# RCservo_interface.net
KiCad netlist of a schematic drawn in Altium Designer
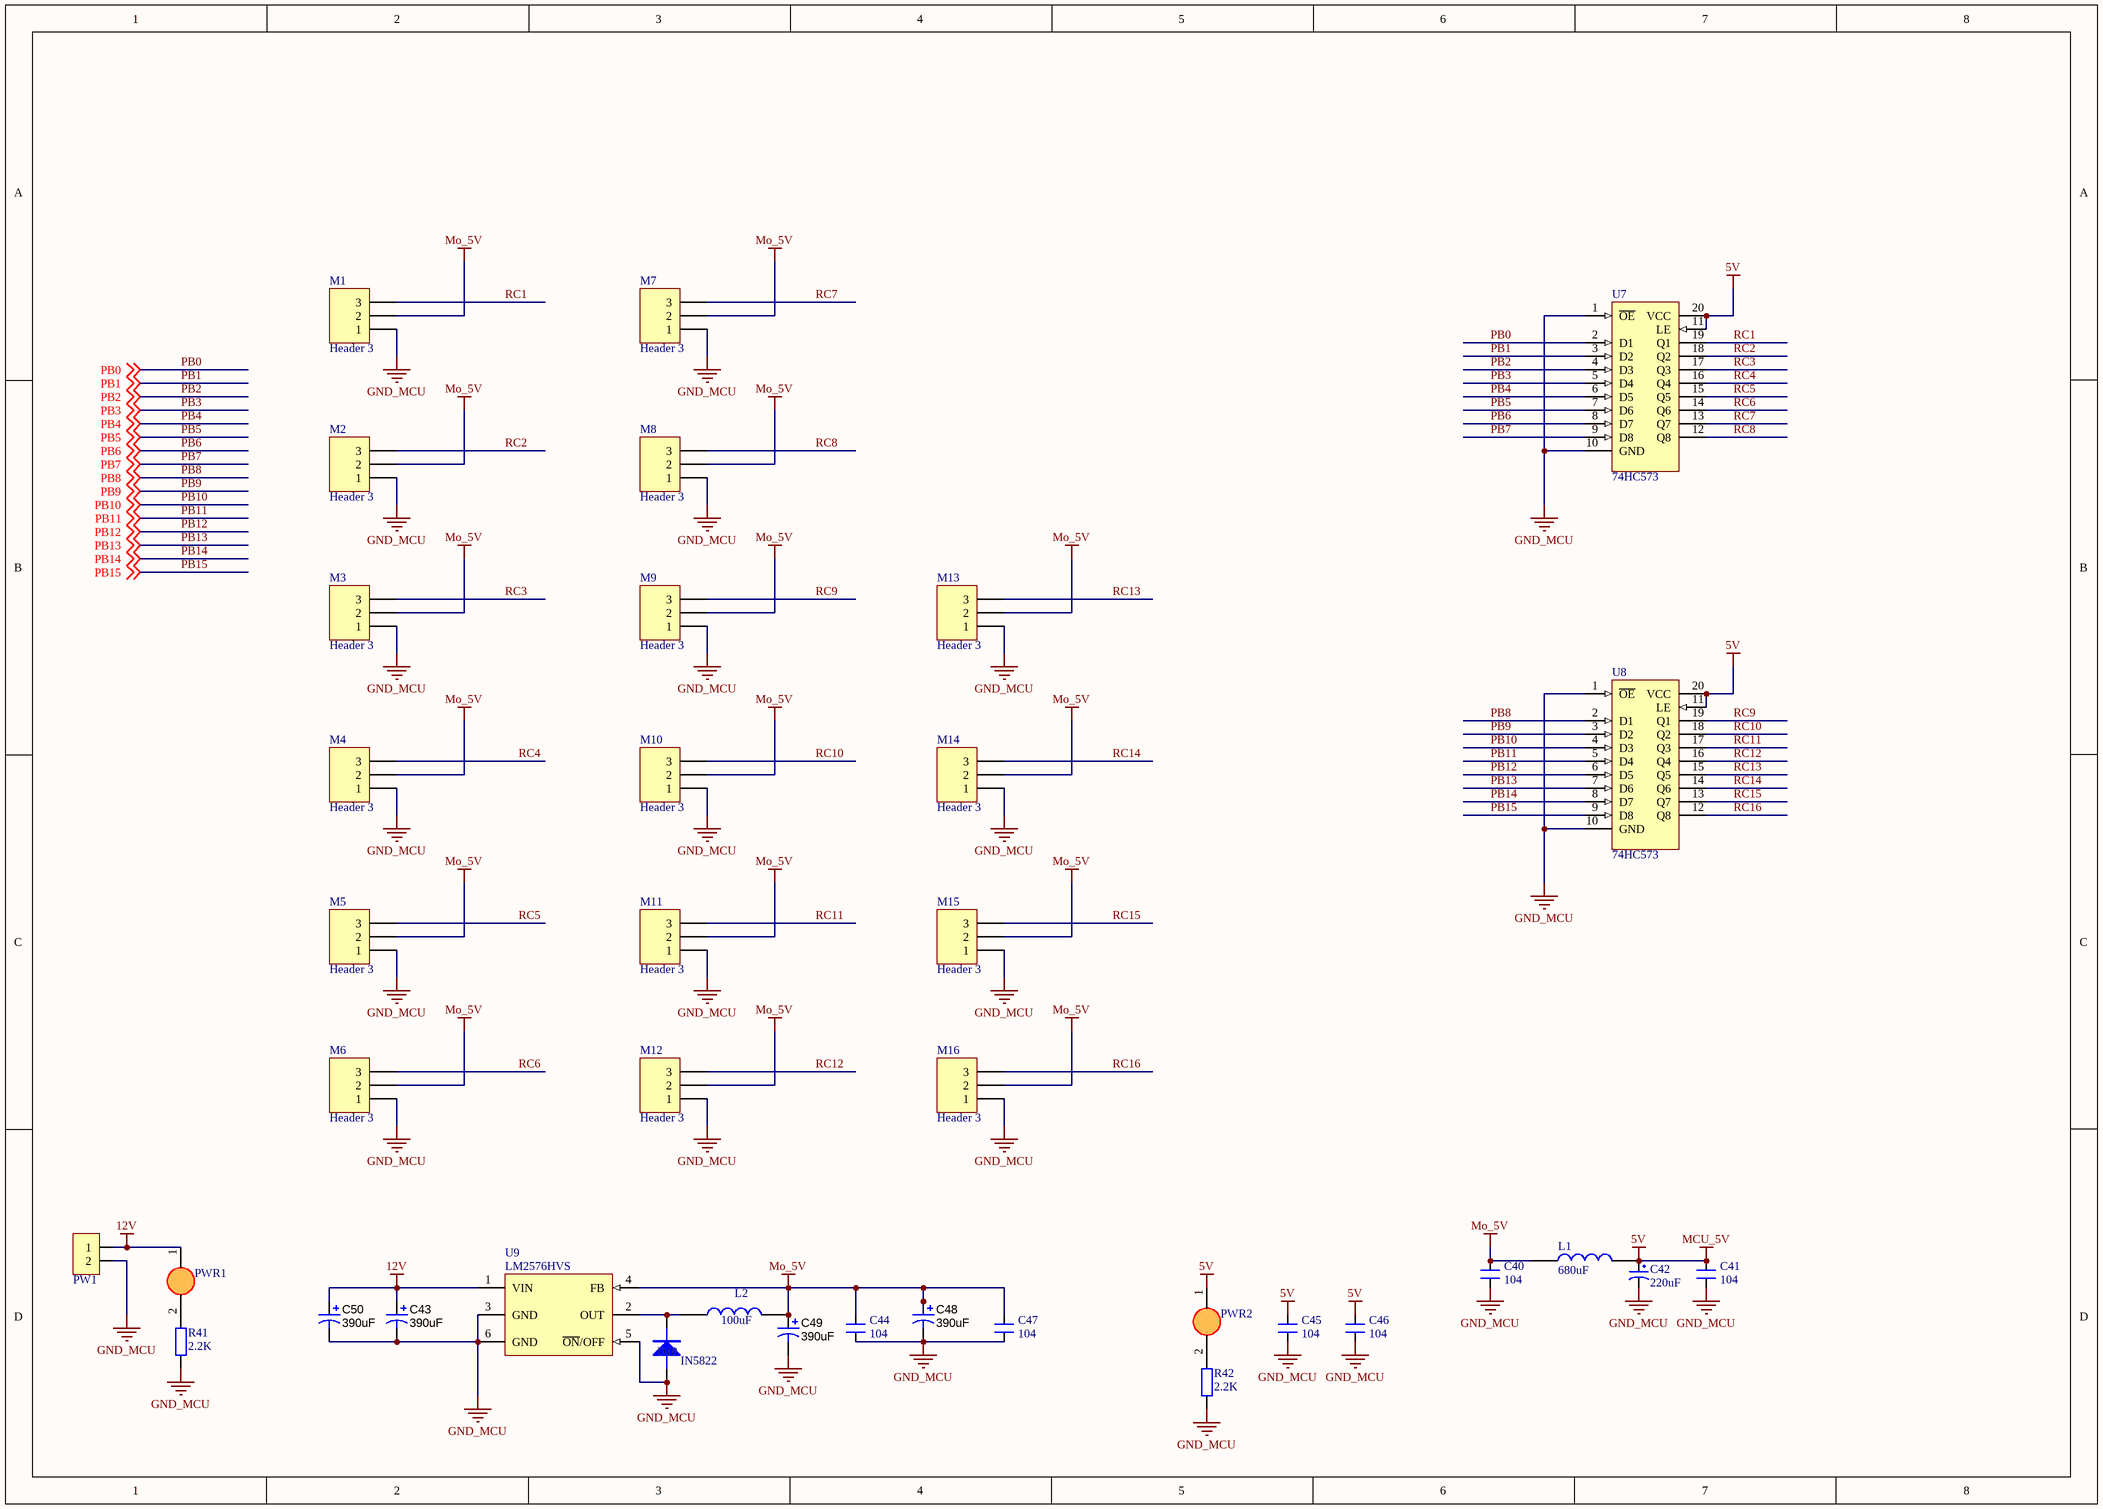
[diagram p0: RCservo_interface.SchDoc]

(export (version "E")
  (design (tool "Eeschema 10.0.6"))
  (components
    (comp (ref "C40")
      (value "104")
      (footprint "0805_HV")
      (description "Cap SMD")
      (libsource (lib "hatcatbietbay") (part "CM"))
    )
    (comp (ref "C41")
      (value "104")
      (footprint "0805_HV")
      (description "Cap SMD")
      (libsource (lib "hatcatbietbay") (part "CM"))
    )
    (comp (ref "C42")
      (value "220uF")
      (footprint "TU_NHOM_2.5_MH")
      (description "TU_NHOM_220uF_25V_MH")
      (libsource (lib "MH_DA_THU_VIEN_16122016") (part "TU_NHOM_220uF_25V_MH"))
    )
    (comp (ref "C43")
      (value "390uF")
      (footprint "CP1/3.0")
      (fields
        (field (name "PARTNUMBER") "UHW1H391MPD6")
        (field (name "MANUFACTURER") "Nichicon")
        (field (name "VALUEDISPLAYED") "390uF")
        (field (name "PUBLISHER") "Texas Instruments")
      )
      (libsource (lib "mySch") (part "Capacitor TuHoa"))
    )
    (comp (ref "C44")
      (value "104")
      (footprint "0805_HV")
      (description "Cap SMD")
      (libsource (lib "hatcatbietbay") (part "CM"))
    )
    (comp (ref "C45")
      (value "104")
      (footprint "0805_HV")
      (description "Cap SMD")
      (libsource (lib "hatcatbietbay") (part "CM"))
    )
    (comp (ref "C46")
      (value "104")
      (footprint "0805_HV")
      (description "Cap SMD")
      (libsource (lib "hatcatbietbay") (part "CM"))
    )
    (comp (ref "C47")
      (value "104")
      (footprint "0805_HV")
      (description "Cap SMD")
      (libsource (lib "hatcatbietbay") (part "CM"))
    )
    (comp (ref "C48")
      (value "390uF")
      (footprint "CP1/3.0")
      (fields
        (field (name "PARTNUMBER") "UHW1H391MPD6")
        (field (name "MANUFACTURER") "Nichicon")
        (field (name "VALUEDISPLAYED") "390uF")
        (field (name "PUBLISHER") "Texas Instruments")
      )
      (libsource (lib "mySch") (part "Capacitor TuHoa"))
    )
    (comp (ref "C49")
      (value "390uF")
      (footprint "CP1/3.0")
      (fields
        (field (name "PARTNUMBER") "UHW1H391MPD6")
        (field (name "MANUFACTURER") "Nichicon")
        (field (name "VALUEDISPLAYED") "390uF")
        (field (name "PUBLISHER") "Texas Instruments")
      )
      (libsource (lib "mySch") (part "Capacitor TuHoa"))
    )
    (comp (ref "C50")
      (value "390uF")
      (footprint "CP1/3.0")
      (fields
        (field (name "PARTNUMBER") "UHW1H391MPD6")
        (field (name "MANUFACTURER") "Nichicon")
        (field (name "VALUEDISPLAYED") "390uF")
        (field (name "PUBLISHER") "Texas Instruments")
      )
      (libsource (lib "mySch") (part "Capacitor TuHoa"))
    )
    (comp (ref "D18")
      (value "IN5822")
      (footprint "SOD123")
      (description "Diode S4 SOD123 ( 1N5819 SOD123)")
      (libsource (lib "MH_DA_THU_VIEN_16122016") (part "Diode S4 SOD123 ( 1N5819 SOD123)_MH"))
    )
    (comp (ref "L1")
      (value "680uF")
      (footprint "Inductor 4.5x5")
      (libsource (lib "MH_DA_THU_VIEN_16122016") (part "Inductor 4.5x5_MH"))
    )
    (comp (ref "L2")
      (value "100uF")
      (footprint "IND_2118-V-RC")
      (description "cuon cam")
      (libsource (lib "MH_DA_THU_VIEN_16122016") (part "Inductor Lm2576_MH"))
    )
    (comp (ref "M1")
      (value "Header 3")
      (footprint "HDR1X3")
      (description "Header, 3-Pin")
      (fields (field (name "PUBLISHER") "Altium Limited"))
      (libsource (lib "Miscellaneous Connectors") (part "Header 3"))
    )
    (comp (ref "M2")
      (value "Header 3")
      (footprint "HDR1X3")
      (description "Header, 3-Pin")
      (fields (field (name "PUBLISHER") "Altium Limited"))
      (libsource (lib "Miscellaneous Connectors") (part "Header 3"))
    )
    (comp (ref "M3")
      (value "Header 3")
      (footprint "HDR1X3")
      (description "Header, 3-Pin")
      (fields (field (name "PUBLISHER") "Altium Limited"))
      (libsource (lib "Miscellaneous Connectors") (part "Header 3"))
    )
    (comp (ref "M4")
      (value "Header 3")
      (footprint "HDR1X3")
      (description "Header, 3-Pin")
      (fields (field (name "PUBLISHER") "Altium Limited"))
      (libsource (lib "Miscellaneous Connectors") (part "Header 3"))
    )
    (comp (ref "M5")
      (value "Header 3")
      (footprint "HDR1X3")
      (description "Header, 3-Pin")
      (fields (field (name "PUBLISHER") "Altium Limited"))
      (libsource (lib "Miscellaneous Connectors") (part "Header 3"))
    )
    (comp (ref "M6")
      (value "Header 3")
      (footprint "HDR1X3")
      (description "Header, 3-Pin")
      (fields (field (name "PUBLISHER") "Altium Limited"))
      (libsource (lib "Miscellaneous Connectors") (part "Header 3"))
    )
    (comp (ref "M7")
      (value "Header 3")
      (footprint "HDR1X3")
      (description "Header, 3-Pin")
      (fields (field (name "PUBLISHER") "Altium Limited"))
      (libsource (lib "Miscellaneous Connectors") (part "Header 3"))
    )
    (comp (ref "M8")
      (value "Header 3")
      (footprint "HDR1X3")
      (description "Header, 3-Pin")
      (fields (field (name "PUBLISHER") "Altium Limited"))
      (libsource (lib "Miscellaneous Connectors") (part "Header 3"))
    )
    (comp (ref "M9")
      (value "Header 3")
      (footprint "HDR1X3")
      (description "Header, 3-Pin")
      (fields (field (name "PUBLISHER") "Altium Limited"))
      (libsource (lib "Miscellaneous Connectors") (part "Header 3"))
    )
    (comp (ref "M10")
      (value "Header 3")
      (footprint "HDR1X3")
      (description "Header, 3-Pin")
      (fields (field (name "PUBLISHER") "Altium Limited"))
      (libsource (lib "Miscellaneous Connectors") (part "Header 3"))
    )
    (comp (ref "M11")
      (value "Header 3")
      (footprint "HDR1X3")
      (description "Header, 3-Pin")
      (fields (field (name "PUBLISHER") "Altium Limited"))
      (libsource (lib "Miscellaneous Connectors") (part "Header 3"))
    )
    (comp (ref "M12")
      (value "Header 3")
      (footprint "HDR1X3")
      (description "Header, 3-Pin")
      (fields (field (name "PUBLISHER") "Altium Limited"))
      (libsource (lib "Miscellaneous Connectors") (part "Header 3"))
    )
    (comp (ref "M13")
      (value "Header 3")
      (footprint "HDR1X3")
      (description "Header, 3-Pin")
      (fields (field (name "PUBLISHER") "Altium Limited"))
      (libsource (lib "Miscellaneous Connectors") (part "Header 3"))
    )
    (comp (ref "M14")
      (value "Header 3")
      (footprint "HDR1X3")
      (description "Header, 3-Pin")
      (fields (field (name "PUBLISHER") "Altium Limited"))
      (libsource (lib "Miscellaneous Connectors") (part "Header 3"))
    )
    (comp (ref "M15")
      (value "Header 3")
      (footprint "HDR1X3")
      (description "Header, 3-Pin")
      (fields (field (name "PUBLISHER") "Altium Limited"))
      (libsource (lib "Miscellaneous Connectors") (part "Header 3"))
    )
    (comp (ref "M16")
      (value "Header 3")
      (footprint "HDR1X3")
      (description "Header, 3-Pin")
      (fields (field (name "PUBLISHER") "Altium Limited"))
      (libsource (lib "Miscellaneous Connectors") (part "Header 3"))
    )
    (comp (ref "PW1")
      (value "CON 2 EDG 5.08_MH")
      (footprint "CON 2 EDG 5.08")
      (description "CON 2 EDG 5.08 (xanh cong)")
      (libsource (lib "MH_DA_THU_VIEN_16122016") (part "CON 2 EDG 5.08_MH"))
    )
    (comp (ref "PWR1")
      (value "LED3")
      (footprint "LED_0805")
      (description "LED 3mm")
      (libsource (lib "MH_DA_THU_VIEN_16122016") (part "LED SMD_0805_MH"))
    )
    (comp (ref "PWR2")
      (value "LED3")
      (footprint "LED_0805")
      (description "LED 3mm")
      (libsource (lib "MH_DA_THU_VIEN_16122016") (part "LED SMD_0805_MH"))
    )
    (comp (ref "R41")
      (value "2.2K")
      (footprint "MH_DA_THU_VIEN_16122016:Tro SMD 0805")
      (description "TRO_SMD_0805_MH")
      (libsource (lib "MH_DA_THU_VIEN_16122016") (part "TRO_SMD_0805_MH"))
    )
    (comp (ref "R42")
      (value "2.2K")
      (footprint "MH_DA_THU_VIEN_16122016:Tro SMD 0805")
      (description "TRO_SMD_0805_MH")
      (libsource (lib "MH_DA_THU_VIEN_16122016") (part "TRO_SMD_0805_MH"))
    )
    (comp (ref "U7")
      (value "74HC573")
      (footprint "SOIC-20")
      (description "Octal D-Type Latch with 3-State Output Non-Inverting")
      (fields (field (name "COPYRIGHT BY") "VanDungEvn@Gmail.com"))
      (libsource (lib "MH_DA_THU_VIEN_16122016") (part "74HC573 DIP20 IC Flip-Flop_MH"))
    )
    (comp (ref "U8")
      (value "74HC573")
      (footprint "SOIC-20")
      (description "Octal D-Type Latch with 3-State Output Non-Inverting")
      (fields (field (name "COPYRIGHT BY") "VanDungEvn@Gmail.com"))
      (libsource (lib "MH_DA_THU_VIEN_16122016") (part "74HC573 DIP20 IC Flip-Flop_MH"))
    )
    (comp (ref "U9")
      (value "LM2576HVS")
      (footprint "TO263-5")
      (description "LM2576HVS-5.0V BUCK 5V 3A TO263-5 _MH")
      (fields
        (field (name "PARTNUMBER") "LM2576T-5.0")
        (field (name "MANUFACTURER") "National Semiconductor")
        (field (name "PUBLISHER") "Altium Limited")
      )
      (libsource (lib "MH_DA_THU_VIEN_16122016") (part "LM2576HVS-5.0V BUCK 5V 3A TO263-5 _MH"))
    )
  )
  (nets
    (net (code "1") (name "/RC1") (class "Default")
      (node (ref "M1") (pin "3") (pinfunction "3_3") (pintype "passive"))
      (node (ref "U7") (pin "19") (pinfunction "Q1_19") (pintype "tri_state"))
    )
    (net (code "2") (name "/RC2") (class "Default")
      (node (ref "M2") (pin "3") (pinfunction "3_3") (pintype "passive"))
      (node (ref "U7") (pin "18") (pinfunction "Q2_18") (pintype "tri_state"))
    )
    (net (code "3") (name "/RC3") (class "Default")
      (node (ref "M3") (pin "3") (pinfunction "3_3") (pintype "passive"))
      (node (ref "U7") (pin "17") (pinfunction "Q3_17") (pintype "tri_state"))
    )
    (net (code "4") (name "/RC4") (class "Default")
      (node (ref "M4") (pin "3") (pinfunction "3_3") (pintype "passive"))
      (node (ref "U7") (pin "16") (pinfunction "Q4_16") (pintype "tri_state"))
    )
    (net (code "5") (name "/RC5") (class "Default")
      (node (ref "M5") (pin "3") (pinfunction "3_3") (pintype "passive"))
      (node (ref "U7") (pin "15") (pinfunction "Q5_15") (pintype "tri_state"))
    )
    (net (code "6") (name "/RC6") (class "Default")
      (node (ref "M6") (pin "3") (pinfunction "3_3") (pintype "passive"))
      (node (ref "U7") (pin "14") (pinfunction "Q6_14") (pintype "tri_state"))
    )
    (net (code "7") (name "/RC7") (class "Default")
      (node (ref "M7") (pin "3") (pinfunction "3_3") (pintype "passive"))
      (node (ref "U7") (pin "13") (pinfunction "Q7_13") (pintype "tri_state"))
    )
    (net (code "8") (name "/RC8") (class "Default")
      (node (ref "M8") (pin "3") (pinfunction "3_3") (pintype "passive"))
      (node (ref "U7") (pin "12") (pinfunction "Q8_12") (pintype "tri_state"))
    )
    (net (code "9") (name "/RC9") (class "Default")
      (node (ref "M9") (pin "3") (pinfunction "3_3") (pintype "passive"))
      (node (ref "U8") (pin "19") (pinfunction "Q1_19") (pintype "tri_state"))
    )
    (net (code "10") (name "/RC10") (class "Default")
      (node (ref "M10") (pin "3") (pinfunction "3_3") (pintype "passive"))
      (node (ref "U8") (pin "18") (pinfunction "Q2_18") (pintype "tri_state"))
    )
    (net (code "11") (name "/RC11") (class "Default")
      (node (ref "M11") (pin "3") (pinfunction "3_3") (pintype "passive"))
      (node (ref "U8") (pin "17") (pinfunction "Q3_17") (pintype "tri_state"))
    )
    (net (code "12") (name "/RC12") (class "Default")
      (node (ref "M12") (pin "3") (pinfunction "3_3") (pintype "passive"))
      (node (ref "U8") (pin "16") (pinfunction "Q4_16") (pintype "tri_state"))
    )
    (net (code "13") (name "/RC13") (class "Default")
      (node (ref "M13") (pin "3") (pinfunction "3_3") (pintype "passive"))
      (node (ref "U8") (pin "15") (pinfunction "Q5_15") (pintype "tri_state"))
    )
    (net (code "14") (name "/RC14") (class "Default")
      (node (ref "M14") (pin "3") (pinfunction "3_3") (pintype "passive"))
      (node (ref "U8") (pin "14") (pinfunction "Q6_14") (pintype "tri_state"))
    )
    (net (code "15") (name "/RC15") (class "Default")
      (node (ref "M15") (pin "3") (pinfunction "3_3") (pintype "passive"))
      (node (ref "U8") (pin "13") (pinfunction "Q7_13") (pintype "tri_state"))
    )
    (net (code "16") (name "/RC16") (class "Default")
      (node (ref "M16") (pin "3") (pinfunction "3_3") (pintype "passive"))
      (node (ref "U8") (pin "12") (pinfunction "Q8_12") (pintype "tri_state"))
    )
    (net (code "17") (name "5V") (class "Default")
      (node (ref "C41") (pin "2") (pinfunction "2_2") (pintype "passive"))
      (node (ref "C42") (pin "1") (pinfunction "1_1") (pintype "passive"))
      (node (ref "C45") (pin "2") (pinfunction "2_2") (pintype "passive"))
      (node (ref "C46") (pin "2") (pinfunction "2_2") (pintype "passive"))
      (node (ref "L1") (pin "2") (pinfunction "2_2") (pintype "passive"))
      (node (ref "PWR2") (pin "1") (pinfunction "A_1") (pintype "passive"))
      (node (ref "U7") (pin "11") (pinfunction "LE_11") (pintype "input"))
      (node (ref "U7") (pin "20") (pinfunction "VCC_20") (pintype "tri_state"))
      (node (ref "U8") (pin "11") (pinfunction "LE_11") (pintype "input"))
      (node (ref "U8") (pin "20") (pinfunction "VCC_20") (pintype "tri_state"))
    )
    (net (code "18") (name "12V") (class "Default")
      (node (ref "C43") (pin "1") (pinfunction "+_1") (pintype "passive"))
      (node (ref "C50") (pin "1") (pinfunction "+_1") (pintype "passive"))
      (node (ref "PW1") (pin "1") (pinfunction "1_1") (pintype "passive"))
      (node (ref "PWR1") (pin "1") (pinfunction "A_1") (pintype "passive"))
      (node (ref "U9") (pin "1") (pinfunction "VIN_1") (pintype "power_in"))
    )
    (net (code "19") (name "GND_MCU") (class "Default")
      (node (ref "C40") (pin "1") (pinfunction "1_1") (pintype "passive"))
      (node (ref "C41") (pin "1") (pinfunction "1_1") (pintype "passive"))
      (node (ref "C42") (pin "2") (pinfunction "2_2") (pintype "passive"))
      (node (ref "C43") (pin "2") (pinfunction "-_2") (pintype "passive"))
      (node (ref "C44") (pin "1") (pinfunction "1_1") (pintype "passive"))
      (node (ref "C45") (pin "1") (pinfunction "1_1") (pintype "passive"))
      (node (ref "C46") (pin "1") (pinfunction "1_1") (pintype "passive"))
      (node (ref "C47") (pin "1") (pinfunction "1_1") (pintype "passive"))
      (node (ref "C48") (pin "2") (pinfunction "-_2") (pintype "passive"))
      (node (ref "C49") (pin "2") (pinfunction "-_2") (pintype "passive"))
      (node (ref "C50") (pin "2") (pinfunction "-_2") (pintype "passive"))
      (node (ref "D18") (pin "1") (pinfunction "1_1") (pintype "passive"))
      (node (ref "M1") (pin "1") (pinfunction "1_1") (pintype "passive"))
      (node (ref "M10") (pin "1") (pinfunction "1_1") (pintype "passive"))
      (node (ref "M11") (pin "1") (pinfunction "1_1") (pintype "passive"))
      (node (ref "M12") (pin "1") (pinfunction "1_1") (pintype "passive"))
      (node (ref "M13") (pin "1") (pinfunction "1_1") (pintype "passive"))
      (node (ref "M14") (pin "1") (pinfunction "1_1") (pintype "passive"))
      (node (ref "M15") (pin "1") (pinfunction "1_1") (pintype "passive"))
      (node (ref "M16") (pin "1") (pinfunction "1_1") (pintype "passive"))
      (node (ref "M2") (pin "1") (pinfunction "1_1") (pintype "passive"))
      (node (ref "M3") (pin "1") (pinfunction "1_1") (pintype "passive"))
      (node (ref "M4") (pin "1") (pinfunction "1_1") (pintype "passive"))
      (node (ref "M5") (pin "1") (pinfunction "1_1") (pintype "passive"))
      (node (ref "M6") (pin "1") (pinfunction "1_1") (pintype "passive"))
      (node (ref "M7") (pin "1") (pinfunction "1_1") (pintype "passive"))
      (node (ref "M8") (pin "1") (pinfunction "1_1") (pintype "passive"))
      (node (ref "M9") (pin "1") (pinfunction "1_1") (pintype "passive"))
      (node (ref "PW1") (pin "2") (pinfunction "2_2") (pintype "passive"))
      (node (ref "R41") (pin "1") (pinfunction "1_1") (pintype "passive"))
      (node (ref "R42") (pin "1") (pinfunction "1_1") (pintype "passive"))
      (node (ref "U7") (pin "1") (pinfunction "~{OE}_1") (pintype "input"))
      (node (ref "U7") (pin "10") (pinfunction "GND_10") (pintype "tri_state"))
      (node (ref "U8") (pin "1") (pinfunction "~{OE}_1") (pintype "input"))
      (node (ref "U8") (pin "10") (pinfunction "GND_10") (pintype "tri_state"))
      (node (ref "U9") (pin "3") (pinfunction "GND_3") (pintype "power_in"))
      (node (ref "U9") (pin "5") (pinfunction "~{ON}/OFF_5") (pintype "input"))
      (node (ref "U9") (pin "6") (pinfunction "GND_6") (pintype "passive"))
    )
    (net (code "20") (name "Mo_5V") (class "Default")
      (node (ref "C40") (pin "2") (pinfunction "2_2") (pintype "passive"))
      (node (ref "C44") (pin "2") (pinfunction "2_2") (pintype "passive"))
      (node (ref "C47") (pin "2") (pinfunction "2_2") (pintype "passive"))
      (node (ref "C48") (pin "1") (pinfunction "+_1") (pintype "passive"))
      (node (ref "C49") (pin "1") (pinfunction "+_1") (pintype "passive"))
      (node (ref "L1") (pin "1") (pinfunction "1_1") (pintype "passive"))
      (node (ref "L2") (pin "2") (pinfunction "2_2") (pintype "passive"))
      (node (ref "M1") (pin "2") (pinfunction "2_2") (pintype "passive"))
      (node (ref "M10") (pin "2") (pinfunction "2_2") (pintype "passive"))
      (node (ref "M11") (pin "2") (pinfunction "2_2") (pintype "passive"))
      (node (ref "M12") (pin "2") (pinfunction "2_2") (pintype "passive"))
      (node (ref "M13") (pin "2") (pinfunction "2_2") (pintype "passive"))
      (node (ref "M14") (pin "2") (pinfunction "2_2") (pintype "passive"))
      (node (ref "M15") (pin "2") (pinfunction "2_2") (pintype "passive"))
      (node (ref "M16") (pin "2") (pinfunction "2_2") (pintype "passive"))
      (node (ref "M2") (pin "2") (pinfunction "2_2") (pintype "passive"))
      (node (ref "M3") (pin "2") (pinfunction "2_2") (pintype "passive"))
      (node (ref "M4") (pin "2") (pinfunction "2_2") (pintype "passive"))
      (node (ref "M5") (pin "2") (pinfunction "2_2") (pintype "passive"))
      (node (ref "M6") (pin "2") (pinfunction "2_2") (pintype "passive"))
      (node (ref "M7") (pin "2") (pinfunction "2_2") (pintype "passive"))
      (node (ref "M8") (pin "2") (pinfunction "2_2") (pintype "passive"))
      (node (ref "M9") (pin "2") (pinfunction "2_2") (pintype "passive"))
      (node (ref "U9") (pin "4") (pinfunction "FB_4") (pintype "input"))
    )
    (net (code "21") (name "Net-(PWR1-K)") (class "Default")
      (node (ref "PWR1") (pin "2") (pinfunction "K_2") (pintype "passive"))
      (node (ref "R41") (pin "2") (pinfunction "2_2") (pintype "passive"))
    )
    (net (code "22") (name "Net-(PWR2-K)") (class "Default")
      (node (ref "PWR2") (pin "2") (pinfunction "K_2") (pintype "passive"))
      (node (ref "R42") (pin "2") (pinfunction "2_2") (pintype "passive"))
    )
    (net (code "23") (name "Net-(U9-OUT)") (class "Default")
      (node (ref "D18") (pin "2") (pinfunction "2_2") (pintype "passive"))
      (node (ref "L2") (pin "1") (pinfunction "1_1") (pintype "passive"))
      (node (ref "U9") (pin "2") (pinfunction "OUT_2") (pintype "power_in"))
    )
    (net (code "24") (name "PB0") (class "Default")
      (node (ref "U7") (pin "2") (pinfunction "D1_2") (pintype "input"))
    )
    (net (code "25") (name "PB1") (class "Default")
      (node (ref "U7") (pin "3") (pinfunction "D2_3") (pintype "input"))
    )
    (net (code "26") (name "PB2") (class "Default")
      (node (ref "U7") (pin "4") (pinfunction "D3_4") (pintype "input"))
    )
    (net (code "27") (name "PB3") (class "Default")
      (node (ref "U7") (pin "5") (pinfunction "D4_5") (pintype "input"))
    )
    (net (code "28") (name "PB4") (class "Default")
      (node (ref "U7") (pin "6") (pinfunction "D5_6") (pintype "input"))
    )
    (net (code "29") (name "PB5") (class "Default")
      (node (ref "U7") (pin "7") (pinfunction "D6_7") (pintype "input"))
    )
    (net (code "30") (name "PB6") (class "Default")
      (node (ref "U7") (pin "8") (pinfunction "D7_8") (pintype "input"))
    )
    (net (code "31") (name "PB7") (class "Default")
      (node (ref "U7") (pin "9") (pinfunction "D8_9") (pintype "input"))
    )
    (net (code "32") (name "PB8") (class "Default")
      (node (ref "U8") (pin "2") (pinfunction "D1_2") (pintype "input"))
    )
    (net (code "33") (name "PB9") (class "Default")
      (node (ref "U8") (pin "3") (pinfunction "D2_3") (pintype "input"))
    )
    (net (code "34") (name "PB10") (class "Default")
      (node (ref "U8") (pin "4") (pinfunction "D3_4") (pintype "input"))
    )
    (net (code "35") (name "PB11") (class "Default")
      (node (ref "U8") (pin "5") (pinfunction "D4_5") (pintype "input"))
    )
    (net (code "36") (name "PB12") (class "Default")
      (node (ref "U8") (pin "6") (pinfunction "D5_6") (pintype "input"))
    )
    (net (code "37") (name "PB13") (class "Default")
      (node (ref "U8") (pin "7") (pinfunction "D6_7") (pintype "input"))
    )
    (net (code "38") (name "PB14") (class "Default")
      (node (ref "U8") (pin "8") (pinfunction "D7_8") (pintype "input"))
    )
    (net (code "39") (name "PB15") (class "Default")
      (node (ref "U8") (pin "9") (pinfunction "D8_9") (pintype "input"))
    )
  )
)
